# pca63557_sheet4_misc.net
KiCad netlist of a schematic drawn in Altium Designer
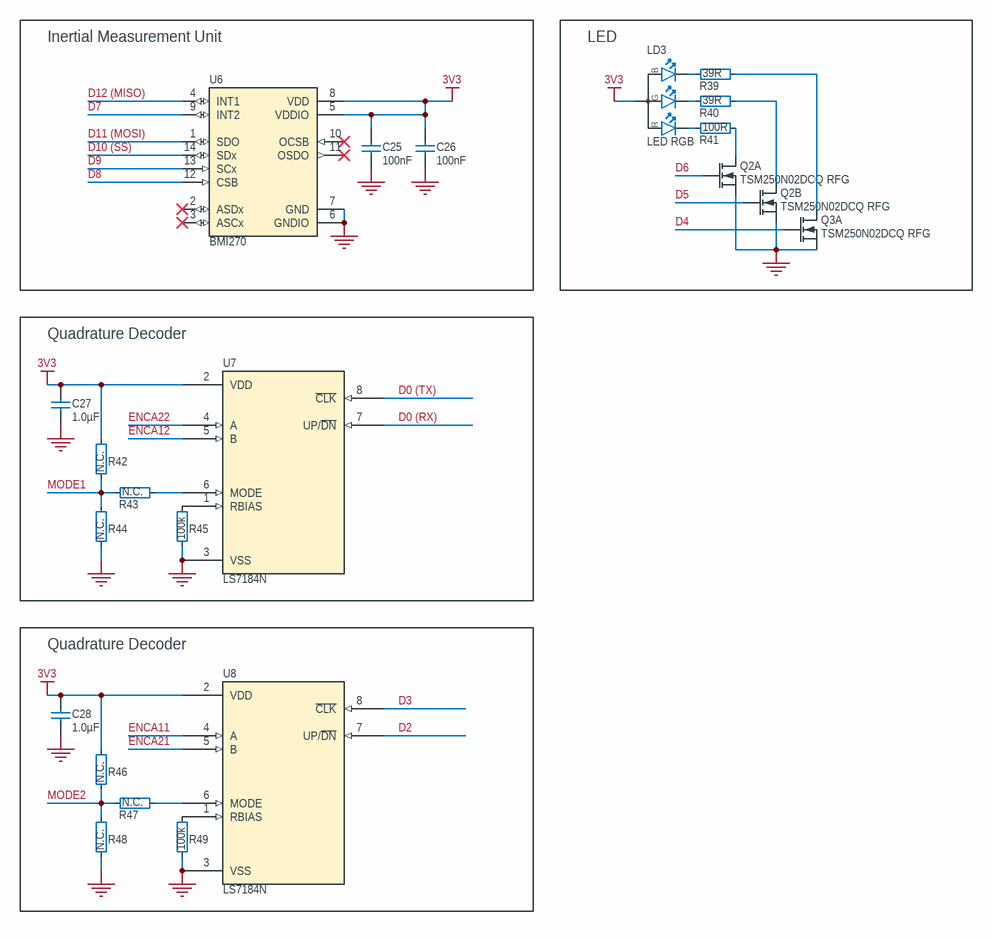
[diagram p0: pca63557_sheet4_misc.SchDoc]

(export (version "E")
  (design (tool "Eeschema 10.0.6"))
  (components
    (comp (ref "C25")
      (value "100nF")
      (footprint "CAPC1005X04L")
      (description "Capacitor, X7R, ±10%")
      (fields
        (field (name "PART NUMBER") "C0402-100n")
        (field (name "MANUFACTURER") "N.A.")
        (field (name "AUTHOR") "rsk")
      )
      (libsource (lib "AltiumLib") (part "CAP"))
    )
    (comp (ref "C26")
      (value "100nF")
      (footprint "CAPC1005X04L")
      (description "Capacitor, X7R, ±10%")
      (fields
        (field (name "PART NUMBER") "C0402-100n")
        (field (name "MANUFACTURER") "N.A.")
        (field (name "AUTHOR") "rsk")
      )
      (libsource (lib "AltiumLib") (part "CAP"))
    )
    (comp (ref "C27")
      (value "1.0µF")
      (footprint "CAPC1005X04L")
      (description "Capacitor, Ceramic, X5R, ±10%, 10V")
      (fields
        (field (name "PART NUMBER") "C0402-1µ0-10V-X5R")
        (field (name "MANUFACTURER") "N.A.")
        (field (name "AUTHOR") "rubr")
      )
      (libsource (lib "AltiumLib") (part "CAP"))
    )
    (comp (ref "C28")
      (value "1.0µF")
      (footprint "CAPC1005X04L")
      (description "Capacitor, Ceramic, X5R, ±10%, 10V")
      (fields
        (field (name "PART NUMBER") "C0402-1µ0-10V-X5R")
        (field (name "MANUFACTURER") "N.A.")
        (field (name "AUTHOR") "rubr")
      )
      (libsource (lib "AltiumLib") (part "CAP"))
    )
    (comp (ref "LD3")
      (value "LED RGB")
      (footprint "LED_RGB_0606")
      (description "RGB LED 1.60 mm x 1.60 mm SMD")
      (fields
        (field (name "PART NUMBER") "LTST-C19HE1WT")
        (field (name "MANUFACTURER") "Lite-On Inc")
        (field (name "AUTHOR") "rsk")
      )
      (libsource (lib "AltiumLib") (part "D{colon}LED_RGB"))
    )
    (comp (ref "Q2")
      (value "TSM250N02DCQ RFG")
      (footprint "DFN65P200X200X80_HS-6N")
      (description "Dual N Ch MOFET, 5.8A, 55mOhm max, 620mW")
      (fields (field (name "MANUFACTURER") "Taiwan Semiconductor") (field (name "AUTHOR") "rsk"))
      (libsource (lib "AltiumLib") (part "T{colon}FET-N-DUAL"))
    )
    (comp (ref "Q3")
      (value "TSM250N02DCQ RFG")
      (footprint "DFN65P200X200X80_HS-6N")
      (description "Dual N Ch MOFET, 5.8A, 55mOhm max, 620mW")
      (fields (field (name "MANUFACTURER") "Taiwan Semiconductor") (field (name "AUTHOR") "rsk"))
      (libsource (lib "AltiumLib") (part "T{colon}FET-N-DUAL"))
    )
    (comp (ref "R39")
      (value "39R")
      (footprint "RESC1005X04L")
      (description "Resistor, ±1%, 0.063W")
      (fields
        (field (name "PART NUMBER") "R0402-39R")
        (field (name "MANUFACTURER") "N.A.")
        (field (name "AUTHOR") "rsk")
      )
      (libsource (lib "AltiumLib") (part "RES"))
    )
    (comp (ref "R40")
      (value "39R")
      (footprint "RESC1005X04L")
      (description "Resistor, ±1%, 0.063W")
      (fields
        (field (name "PART NUMBER") "R0402-39R")
        (field (name "MANUFACTURER") "N.A.")
        (field (name "AUTHOR") "rsk")
      )
      (libsource (lib "AltiumLib") (part "RES"))
    )
    (comp (ref "R41")
      (value "100R")
      (footprint "RESC1005X04L")
      (description "Resistor, ±1%, 0.063W")
      (fields
        (field (name "PART NUMBER") "R0402-100")
        (field (name "MANUFACTURER") "N.A.")
        (field (name "AUTHOR") "rsk")
      )
      (libsource (lib "AltiumLib") (part "RES"))
    )
    (comp (ref "R42")
      (value "N.C.")
      (footprint "RESC1005X04L_NC")
      (description "Not mounted")
      (fields
        (field (name "PART NUMBER") "R0402-N.C.")
        (field (name "MANUFACTURER") "N.A.")
        (field (name "AUTHOR") "rsk")
      )
      (libsource (lib "AltiumLib") (part "RES"))
    )
    (comp (ref "R43")
      (value "N.C.")
      (footprint "RESC1005X04L_NC")
      (description "Not mounted")
      (fields
        (field (name "PART NUMBER") "R0402-N.C.")
        (field (name "MANUFACTURER") "N.A.")
        (field (name "AUTHOR") "rsk")
      )
      (libsource (lib "AltiumLib") (part "RES"))
    )
    (comp (ref "R44")
      (value "N.C.")
      (footprint "RESC1005X04L_NC")
      (description "Not mounted")
      (fields
        (field (name "PART NUMBER") "R0402-N.C.")
        (field (name "MANUFACTURER") "N.A.")
        (field (name "AUTHOR") "rsk")
      )
      (libsource (lib "AltiumLib") (part "RES"))
    )
    (comp (ref "R45")
      (value "100k")
      (footprint "RESC1005X04L")
      (description "Resistor, ±1%, 0.063W")
      (fields
        (field (name "PART NUMBER") "R0402-100k")
        (field (name "MANUFACTURER") "N.A.")
        (field (name "AUTHOR") "rsk")
      )
      (libsource (lib "AltiumLib") (part "RES"))
    )
    (comp (ref "R46")
      (value "N.C.")
      (footprint "RESC1005X04L_NC")
      (description "Not mounted")
      (fields
        (field (name "PART NUMBER") "R0402-N.C.")
        (field (name "MANUFACTURER") "N.A.")
        (field (name "AUTHOR") "rsk")
      )
      (libsource (lib "AltiumLib") (part "RES"))
    )
    (comp (ref "R47")
      (value "N.C.")
      (footprint "RESC1005X04L_NC")
      (description "Not mounted")
      (fields
        (field (name "PART NUMBER") "R0402-N.C.")
        (field (name "MANUFACTURER") "N.A.")
        (field (name "AUTHOR") "rsk")
      )
      (libsource (lib "AltiumLib") (part "RES"))
    )
    (comp (ref "R48")
      (value "N.C.")
      (footprint "RESC1005X04L_NC")
      (description "Not mounted")
      (fields
        (field (name "PART NUMBER") "R0402-N.C.")
        (field (name "MANUFACTURER") "N.A.")
        (field (name "AUTHOR") "rsk")
      )
      (libsource (lib "AltiumLib") (part "RES"))
    )
    (comp (ref "R49")
      (value "100k")
      (footprint "RESC1005X04L")
      (description "Resistor, ±1%, 0.063W")
      (fields
        (field (name "PART NUMBER") "R0402-100k")
        (field (name "MANUFACTURER") "N.A.")
        (field (name "AUTHOR") "rsk")
      )
      (libsource (lib "AltiumLib") (part "RES"))
    )
    (comp (ref "U6")
      (value "BMI270")
      (footprint "BMI270")
      (description "6-axis, smart, low-power, inertial measurement unit")
      (fields (field (name "MANUFACTURER") "Bosch") (field (name "AUTHOR") "rsk"))
      (libsource (lib "AltiumLib") (part "BMI270"))
    )
    (comp (ref "U7")
      (value "LS7184N")
      (footprint "LS7184N")
      (description "QUADRATURE CLOCK CONVERTER")
      (fields
        (field (name "MANUFACTURER") "LSI/CSI")
        (field (name "MANUFACTURER PART NUMBER") "LS7184N-S")
        (field (name "AUTHOR") "mam1")
      )
      (libsource (lib "AltiumLib") (part "LS7184N"))
    )
    (comp (ref "U8")
      (value "LS7184N")
      (footprint "LS7184N")
      (description "QUADRATURE CLOCK CONVERTER")
      (fields
        (field (name "MANUFACTURER") "LSI/CSI")
        (field (name "MANUFACTURER PART NUMBER") "LS7184N-S")
        (field (name "AUTHOR") "mam1")
      )
      (libsource (lib "AltiumLib") (part "LS7184N"))
    )
  )
  (nets
    (net (code "1") (name "/D0 (RX)") (class "Default")
      (node (ref "U7") (pin "7") (pinfunction "UP/~{DN}_7") (pintype "input"))
    )
    (net (code "2") (name "/D0 (TX)") (class "Default")
      (node (ref "U7") (pin "8") (pinfunction "~{CLK}_8") (pintype "input"))
    )
    (net (code "3") (name "/D2") (class "Default")
      (node (ref "U8") (pin "7") (pinfunction "UP/~{DN}_7") (pintype "input"))
    )
    (net (code "4") (name "/D3") (class "Default")
      (node (ref "U8") (pin "8") (pinfunction "~{CLK}_8") (pintype "input"))
    )
    (net (code "5") (name "/D4") (class "Default")
      (node (ref "Q3") (pin "2") (pinfunction "G1_2") (pintype "passive"))
    )
    (net (code "6") (name "/D5") (class "Default")
      (node (ref "Q2") (pin "5") (pinfunction "G2_5") (pintype "passive"))
    )
    (net (code "7") (name "/D6") (class "Default")
      (node (ref "Q2") (pin "2") (pinfunction "G1_2") (pintype "passive"))
    )
    (net (code "8") (name "/D7") (class "Default")
      (node (ref "U6") (pin "9") (pinfunction "INT2_9") (pintype "bidirectional"))
    )
    (net (code "9") (name "/D8") (class "Default")
      (node (ref "U6") (pin "12") (pinfunction "CSB_12") (pintype "input"))
    )
    (net (code "10") (name "/D9") (class "Default")
      (node (ref "U6") (pin "13") (pinfunction "SCx_13") (pintype "input"))
    )
    (net (code "11") (name "/D10 (SS)") (class "Default")
      (node (ref "U6") (pin "14") (pinfunction "SDx_14") (pintype "bidirectional"))
    )
    (net (code "12") (name "/D11 (MOSI)") (class "Default")
      (node (ref "U6") (pin "1") (pinfunction "SDO_1") (pintype "bidirectional"))
    )
    (net (code "13") (name "/D12 (MISO)") (class "Default")
      (node (ref "U6") (pin "4") (pinfunction "INT1_4") (pintype "bidirectional"))
    )
    (net (code "14") (name "/ENCA11") (class "Default")
      (node (ref "U8") (pin "4") (pinfunction "A_4") (pintype "input"))
    )
    (net (code "15") (name "/ENCA12") (class "Default")
      (node (ref "U7") (pin "5") (pinfunction "B_5") (pintype "input"))
    )
    (net (code "16") (name "/ENCA21") (class "Default")
      (node (ref "U8") (pin "5") (pinfunction "B_5") (pintype "input"))
    )
    (net (code "17") (name "/ENCA22") (class "Default")
      (node (ref "U7") (pin "4") (pinfunction "A_4") (pintype "input"))
    )
    (net (code "18") (name "/MODE1") (class "Default")
      (node (ref "R42") (pin "1") (pinfunction "1_1") (pintype "passive"))
      (node (ref "R43") (pin "1") (pinfunction "1_1") (pintype "passive"))
      (node (ref "R44") (pin "2") (pinfunction "2_2") (pintype "passive"))
    )
    (net (code "19") (name "/MODE2") (class "Default")
      (node (ref "R46") (pin "1") (pinfunction "1_1") (pintype "passive"))
      (node (ref "R47") (pin "1") (pinfunction "1_1") (pintype "passive"))
      (node (ref "R48") (pin "2") (pinfunction "2_2") (pintype "passive"))
    )
    (net (code "20") (name "3V3") (class "Default")
      (node (ref "C25") (pin "2") (pinfunction "2_2") (pintype "passive"))
      (node (ref "C26") (pin "2") (pinfunction "2_2") (pintype "passive"))
      (node (ref "C27") (pin "2") (pinfunction "2_2") (pintype "passive"))
      (node (ref "C28") (pin "2") (pinfunction "2_2") (pintype "passive"))
      (node (ref "LD3") (pin "4") (pinfunction "A_4") (pintype "passive"))
      (node (ref "R42") (pin "2") (pinfunction "2_2") (pintype "passive"))
      (node (ref "R46") (pin "2") (pinfunction "2_2") (pintype "passive"))
      (node (ref "U6") (pin "5") (pinfunction "VDDIO_5") (pintype "power_in"))
      (node (ref "U6") (pin "8") (pinfunction "VDD_8") (pintype "power_in"))
      (node (ref "U7") (pin "2") (pinfunction "VDD_2") (pintype "power_in"))
      (node (ref "U8") (pin "2") (pinfunction "VDD_2") (pintype "power_in"))
    )
    (net (code "21") (name "GND") (class "Default")
      (node (ref "C25") (pin "1") (pinfunction "1_1") (pintype "passive"))
      (node (ref "C26") (pin "1") (pinfunction "1_1") (pintype "passive"))
      (node (ref "C27") (pin "1") (pinfunction "1_1") (pintype "passive"))
      (node (ref "C28") (pin "1") (pinfunction "1_1") (pintype "passive"))
      (node (ref "Q2") (pin "1") (pinfunction "S1_1") (pintype "passive"))
      (node (ref "Q2") (pin "4") (pinfunction "S2_4") (pintype "passive"))
      (node (ref "Q3") (pin "1") (pinfunction "S1_1") (pintype "passive"))
      (node (ref "R44") (pin "1") (pinfunction "1_1") (pintype "passive"))
      (node (ref "R45") (pin "1") (pinfunction "1_1") (pintype "passive"))
      (node (ref "R48") (pin "1") (pinfunction "1_1") (pintype "passive"))
      (node (ref "R49") (pin "1") (pinfunction "1_1") (pintype "passive"))
      (node (ref "U6") (pin "6") (pinfunction "GNDIO_6") (pintype "power_in"))
      (node (ref "U6") (pin "7") (pinfunction "GND_7") (pintype "power_in"))
      (node (ref "U7") (pin "3") (pinfunction "VSS_3") (pintype "power_in"))
      (node (ref "U8") (pin "3") (pinfunction "VSS_3") (pintype "power_in"))
    )
    (net (code "22") (name "Net-(LD3-C_BLUE)") (class "Default")
      (node (ref "LD3") (pin "3") (pinfunction "C_BLUE_3") (pintype "passive"))
      (node (ref "R39") (pin "1") (pinfunction "1_1") (pintype "passive"))
    )
    (net (code "23") (name "Net-(LD3-C_GREEN)") (class "Default")
      (node (ref "LD3") (pin "2") (pinfunction "C_GREEN_2") (pintype "passive"))
      (node (ref "R40") (pin "1") (pinfunction "1_1") (pintype "passive"))
    )
    (net (code "24") (name "Net-(LD3-C_RED)") (class "Default")
      (node (ref "LD3") (pin "1") (pinfunction "C_RED_1") (pintype "passive"))
      (node (ref "R41") (pin "1") (pinfunction "1_1") (pintype "passive"))
    )
    (net (code "25") (name "Net-(Q2A-D1)") (class "Default")
      (node (ref "Q2") (pin "6") (pinfunction "D1_6") (pintype "passive"))
      (node (ref "R41") (pin "2") (pinfunction "2_2") (pintype "passive"))
    )
    (net (code "26") (name "Net-(Q2B-D2)") (class "Default")
      (node (ref "Q2") (pin "3") (pinfunction "D2_3") (pintype "passive"))
      (node (ref "R40") (pin "2") (pinfunction "2_2") (pintype "passive"))
    )
    (net (code "27") (name "Net-(Q3A-D1)") (class "Default")
      (node (ref "Q3") (pin "6") (pinfunction "D1_6") (pintype "passive"))
      (node (ref "R39") (pin "2") (pinfunction "2_2") (pintype "passive"))
    )
    (net (code "28") (name "Net-(U7-MODE)") (class "Default")
      (node (ref "R43") (pin "2") (pinfunction "2_2") (pintype "passive"))
      (node (ref "U7") (pin "6") (pinfunction "MODE_6") (pintype "input"))
    )
    (net (code "29") (name "Net-(U7-RBIAS)") (class "Default")
      (node (ref "R45") (pin "2") (pinfunction "2_2") (pintype "passive"))
      (node (ref "U7") (pin "1") (pinfunction "RBIAS_1") (pintype "input"))
    )
    (net (code "30") (name "Net-(U8-MODE)") (class "Default")
      (node (ref "R47") (pin "2") (pinfunction "2_2") (pintype "passive"))
      (node (ref "U8") (pin "6") (pinfunction "MODE_6") (pintype "input"))
    )
    (net (code "31") (name "Net-(U8-RBIAS)") (class "Default")
      (node (ref "R49") (pin "2") (pinfunction "2_2") (pintype "passive"))
      (node (ref "U8") (pin "1") (pinfunction "RBIAS_1") (pintype "input"))
    )
    (net (code "32") (name "unconnected-(U6-ASCx-Pad3)") (class "Default")
      (node (ref "U6") (pin "3") (pinfunction "ASCx_3") (pintype "bidirectional+no_connect"))
    )
    (net (code "33") (name "unconnected-(U6-ASDx-Pad2)") (class "Default")
      (node (ref "U6") (pin "2") (pinfunction "ASDx_2") (pintype "bidirectional+no_connect"))
    )
    (net (code "34") (name "unconnected-(U6-OCSB-Pad10)") (class "Default")
      (node (ref "U6") (pin "10") (pinfunction "OCSB_10") (pintype "input+no_connect"))
    )
    (net (code "35") (name "unconnected-(U6-OSDO-Pad11)") (class "Default")
      (node (ref "U6") (pin "11") (pinfunction "OSDO_11") (pintype "output+no_connect"))
    )
  )
)
